# Rover-8_Power_Supply.net
KiCad netlist of a schematic drawn in EAGLE
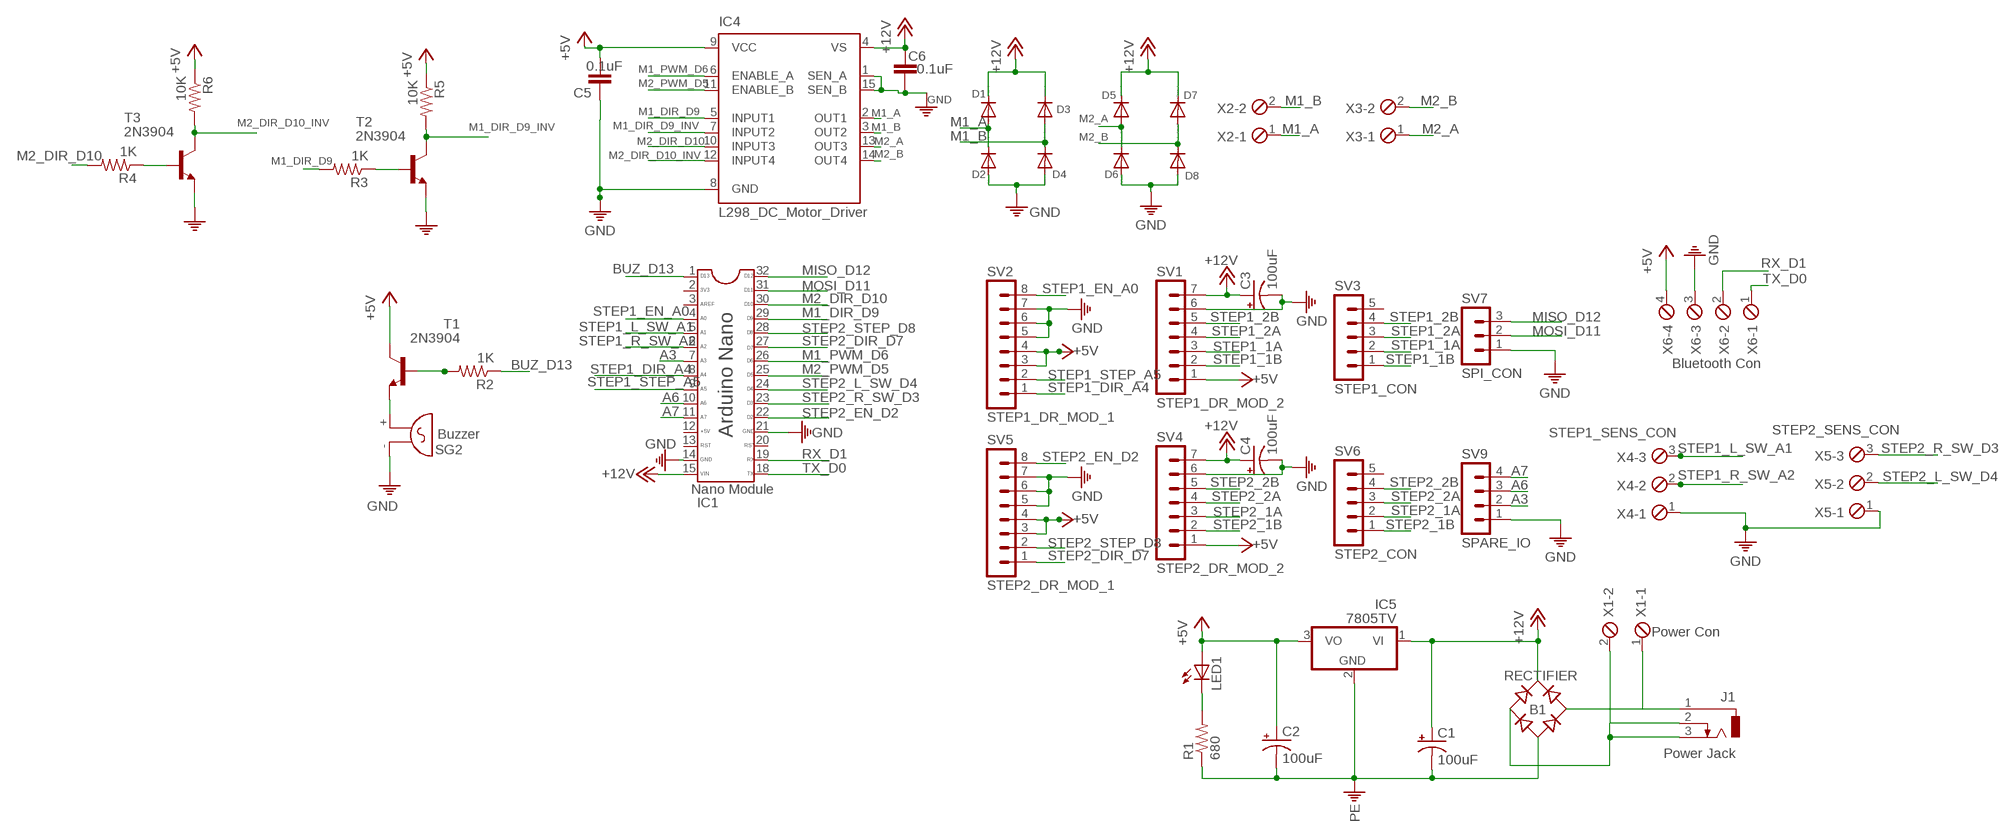
[diagram p0: schematic, sheet 1]

(export (version "E")
  (design (tool "Eeschema 10.0.6"))
  (components
    (comp (ref "B1")
      (value "RECTIFIER")
      (footprint "eagle-import:RB1A")
      (libsource (lib "eagle-import") (part "RB1A"))
    )
    (comp (ref "C1")
      (value "100uF")
      (footprint "eagle-import:E1,8-4")
      (libsource (lib "eagle-import") (part "CPOL-USE1.8-4"))
    )
    (comp (ref "C2")
      (value "100uF")
      (footprint "eagle-import:E1,8-4")
      (libsource (lib "eagle-import") (part "CPOL-USE1.8-4"))
    )
    (comp (ref "C3")
      (value "100uF")
      (footprint "eagle-import:E1,8-4")
      (libsource (lib "eagle-import") (part "CPOL-USE1.8-4"))
    )
    (comp (ref "C4")
      (value "100uF")
      (footprint "eagle-import:E1,8-4")
      (libsource (lib "eagle-import") (part "CPOL-USE1.8-4"))
    )
    (comp (ref "C5")
      (value "0.1uF")
      (footprint "eagle-import:C025-024X044")
      (libsource (lib "eagle-import") (part "C-EU025-024X044"))
    )
    (comp (ref "C6")
      (value "0.1uF")
      (footprint "eagle-import:C025-024X044")
      (libsource (lib "eagle-import") (part "C-EU025-024X044"))
    )
    (comp (ref "D1")
      (value "DIODE-D-2.5")
      (footprint "eagle-import:D-2.5")
      (libsource (lib "eagle-import") (part "DIODE-D-2.5"))
    )
    (comp (ref "D2")
      (value "DIODE-D-2.5")
      (footprint "eagle-import:D-2.5")
      (libsource (lib "eagle-import") (part "DIODE-D-2.5"))
    )
    (comp (ref "D3")
      (value "DIODE-D-2.5")
      (footprint "eagle-import:D-2.5")
      (libsource (lib "eagle-import") (part "DIODE-D-2.5"))
    )
    (comp (ref "D4")
      (value "DIODE-D-2.5")
      (footprint "eagle-import:D-2.5")
      (libsource (lib "eagle-import") (part "DIODE-D-2.5"))
    )
    (comp (ref "D5")
      (value "DIODE-D-2.5")
      (footprint "eagle-import:D-2.5")
      (libsource (lib "eagle-import") (part "DIODE-D-2.5"))
    )
    (comp (ref "D6")
      (value "DIODE-D-2.5")
      (footprint "eagle-import:D-2.5")
      (libsource (lib "eagle-import") (part "DIODE-D-2.5"))
    )
    (comp (ref "D7")
      (value "DIODE-D-2.5")
      (footprint "eagle-import:D-2.5")
      (libsource (lib "eagle-import") (part "DIODE-D-2.5"))
    )
    (comp (ref "D8")
      (value "DIODE-D-2.5")
      (footprint "eagle-import:D-2.5")
      (libsource (lib "eagle-import") (part "DIODE-D-2.5"))
    )
    (comp (ref "IC1")
      (value "Nano Module")
      (footprint "eagle-import:DIL32")
      (libsource (lib "eagle-import") (part "DIL32"))
    )
    (comp (ref "IC4")
      (value "L298_DC_Motor_Driver")
      (footprint "eagle-import:MULTIWATT-15")
      (fields (field (name "MPN") "L298N"))
      (libsource (lib "eagle-import") (part "L298"))
    )
    (comp (ref "IC5")
      (value "7805TV")
      (footprint "eagle-import:TO220V")
      (libsource (lib "eagle-import") (part "78TV05"))
    )
    (comp (ref "J1")
      (value "Power Jack")
      (footprint "eagle-import:ROVER-PW-JACL")
      (libsource (lib "eagle-import") (part "DCJ0303"))
    )
    (comp (ref "LED1")
      (value "LED3MM")
      (footprint "eagle-import:LED3MM")
      (libsource (lib "eagle-import") (part "LED3MM"))
    )
    (comp (ref "R1")
      (value "680")
      (footprint "eagle-import:0204_5")
      (libsource (lib "eagle-import") (part "R-US_0204/5"))
    )
    (comp (ref "R2")
      (value "1K")
      (footprint "eagle-import:0204_5")
      (libsource (lib "eagle-import") (part "R-US_0204/5"))
    )
    (comp (ref "R3")
      (value "1K")
      (footprint "eagle-import:0204_5")
      (libsource (lib "eagle-import") (part "R-US_0204/5"))
    )
    (comp (ref "R4")
      (value "1K")
      (footprint "eagle-import:0204_5")
      (libsource (lib "eagle-import") (part "R-US_0204/5"))
    )
    (comp (ref "R5")
      (value "10K")
      (footprint "eagle-import:0204_5")
      (libsource (lib "eagle-import") (part "R-US_0204/5"))
    )
    (comp (ref "R6")
      (value "10K")
      (footprint "eagle-import:0204_5")
      (libsource (lib "eagle-import") (part "R-US_0204/5"))
    )
    (comp (ref "SG2")
      (value "Buzzer")
      (footprint "eagle-import:F_QMX")
      (libsource (lib "eagle-import") (part "F/QMX"))
    )
    (comp (ref "SV1")
      (value "STEP1_DR_MOD_2")
      (footprint "eagle-import:MA07-1")
      (libsource (lib "eagle-import") (part "MA07-1"))
    )
    (comp (ref "SV2")
      (value "STEP1_DR_MOD_1")
      (footprint "eagle-import:MA08-1")
      (libsource (lib "eagle-import") (part "MA08-1"))
    )
    (comp (ref "SV3")
      (value "STEP1_CON")
      (footprint "eagle-import:MA05-1")
      (libsource (lib "eagle-import") (part "MA05-1"))
    )
    (comp (ref "SV4")
      (value "STEP2_DR_MOD_2")
      (footprint "eagle-import:MA07-1")
      (libsource (lib "eagle-import") (part "MA07-1"))
    )
    (comp (ref "SV5")
      (value "STEP2_DR_MOD_1")
      (footprint "eagle-import:MA08-1")
      (libsource (lib "eagle-import") (part "MA08-1"))
    )
    (comp (ref "SV6")
      (value "STEP2_CON")
      (footprint "eagle-import:MA05-1")
      (libsource (lib "eagle-import") (part "MA05-1"))
    )
    (comp (ref "SV7")
      (value "SPI_CON")
      (footprint "eagle-import:MA03-1")
      (libsource (lib "eagle-import") (part "MA03-1"))
    )
    (comp (ref "SV9")
      (value "SPARE_IO")
      (footprint "eagle-import:MA04-1")
      (libsource (lib "eagle-import") (part "MA04-1"))
    )
    (comp (ref "T1")
      (value "2N3904")
      (footprint "eagle-import:TO92")
      (libsource (lib "eagle-import") (part "2N3904"))
    )
    (comp (ref "T2")
      (value "2N3904")
      (footprint "eagle-import:TO92")
      (libsource (lib "eagle-import") (part "2N3904"))
    )
    (comp (ref "T3")
      (value "2N3904")
      (footprint "eagle-import:TO92")
      (libsource (lib "eagle-import") (part "2N3904"))
    )
    (comp (ref "X1")
      (value "Power Con")
      (footprint "eagle-import:2POL254")
      (libsource (lib "eagle-import") (part "MPT2"))
    )
    (comp (ref "X2")
      (value "MPT2")
      (footprint "eagle-import:2POL254")
      (libsource (lib "eagle-import") (part "MPT2"))
    )
    (comp (ref "X3")
      (value "MPT2")
      (footprint "eagle-import:2POL254")
      (libsource (lib "eagle-import") (part "MPT2"))
    )
    (comp (ref "X4")
      (value "STEP1_SENS_CON")
      (footprint "eagle-import:3POL254")
      (libsource (lib "eagle-import") (part "MPT3"))
    )
    (comp (ref "X5")
      (value "STEP2_SENS_CON")
      (footprint "eagle-import:3POL254")
      (libsource (lib "eagle-import") (part "MPT3"))
    )
    (comp (ref "X6")
      (value "Bluetooth Con")
      (footprint "eagle-import:4POL254")
      (libsource (lib "eagle-import") (part "MPT4"))
    )
  )
  (nets
    (net (code "1") (name "+5V") (class "Default")
      (node (ref "C2") (pin "+") (pinfunction "+_+") (pintype "passive"))
      (node (ref "C5") (pin "2") (pinfunction "2_2") (pintype "passive"))
      (node (ref "IC4") (pin "9") (pinfunction "VCC_9") (pintype "power_in"))
      (node (ref "IC5") (pin "3") (pinfunction "VO_3") (pintype "passive"))
      (node (ref "LED1") (pin "A") (pinfunction "A_A") (pintype "passive"))
      (node (ref "R5") (pin "1") (pinfunction "1_1") (pintype "passive"))
      (node (ref "R6") (pin "1") (pinfunction "1_1") (pintype "passive"))
      (node (ref "SV1") (pin "1") (pinfunction "1_1") (pintype "passive"))
      (node (ref "SV2") (pin "3") (pinfunction "3_3") (pintype "passive"))
      (node (ref "SV2") (pin "4") (pinfunction "4_4") (pintype "passive"))
      (node (ref "SV4") (pin "1") (pinfunction "1_1") (pintype "passive"))
      (node (ref "SV5") (pin "3") (pinfunction "3_3") (pintype "passive"))
      (node (ref "SV5") (pin "4") (pinfunction "4_4") (pintype "passive"))
      (node (ref "T1") (pin "1") (pinfunction "C_1") (pintype "passive"))
      (node (ref "X6") (pin "4") (pinfunction "1_4") (pintype "passive"))
    )
    (net (code "2") (name "+12V") (class "Default")
      (node (ref "B1") (pin "+") (pinfunction "+_+") (pintype "passive"))
      (node (ref "C1") (pin "+") (pinfunction "+_+") (pintype "passive"))
      (node (ref "C3") (pin "+") (pinfunction "+_+") (pintype "passive"))
      (node (ref "C4") (pin "+") (pinfunction "+_+") (pintype "passive"))
      (node (ref "C6") (pin "2") (pinfunction "2_2") (pintype "passive"))
      (node (ref "D1") (pin "C") (pinfunction "C_C") (pintype "passive"))
      (node (ref "D3") (pin "C") (pinfunction "C_C") (pintype "passive"))
      (node (ref "D5") (pin "C") (pinfunction "C_C") (pintype "passive"))
      (node (ref "D7") (pin "C") (pinfunction "C_C") (pintype "passive"))
      (node (ref "IC1") (pin "15") (pinfunction "VIN_15") (pintype "passive"))
      (node (ref "IC4") (pin "4") (pinfunction "VS_4") (pintype "power_in"))
      (node (ref "IC5") (pin "1") (pinfunction "VI_1") (pintype "input"))
      (node (ref "SV1") (pin "7") (pinfunction "7_7") (pintype "passive"))
      (node (ref "SV4") (pin "7") (pinfunction "7_7") (pintype "passive"))
    )
    (net (code "3") (name "/A3") (class "Default")
      (node (ref "IC1") (pin "7") (pinfunction "A3/D17_7") (pintype "passive"))
      (node (ref "SV9") (pin "2") (pinfunction "2_2") (pintype "passive"))
    )
    (net (code "4") (name "/A6") (class "Default")
      (node (ref "IC1") (pin "10") (pinfunction "A6_10") (pintype "passive"))
      (node (ref "SV9") (pin "3") (pinfunction "3_3") (pintype "passive"))
    )
    (net (code "5") (name "/A7") (class "Default")
      (node (ref "IC1") (pin "11") (pinfunction "A7_11") (pintype "passive"))
      (node (ref "SV9") (pin "4") (pinfunction "4_4") (pintype "passive"))
    )
    (net (code "6") (name "/BUZ_D13") (class "Default")
      (node (ref "IC1") (pin "1") (pinfunction "D13_1") (pintype "passive"))
      (node (ref "R2") (pin "1") (pinfunction "1_1") (pintype "passive"))
    )
    (net (code "7") (name "/M1_A") (class "Default")
      (node (ref "D1") (pin "A") (pinfunction "A_A") (pintype "passive"))
      (node (ref "D2") (pin "C") (pinfunction "C_C") (pintype "passive"))
      (node (ref "IC4") (pin "2") (pinfunction "OUT1_2") (pintype "output"))
      (node (ref "X2") (pin "1") (pinfunction "1_1") (pintype "passive"))
    )
    (net (code "8") (name "/M1_B") (class "Default")
      (node (ref "D3") (pin "A") (pinfunction "A_A") (pintype "passive"))
      (node (ref "D4") (pin "C") (pinfunction "C_C") (pintype "passive"))
      (node (ref "IC4") (pin "3") (pinfunction "OUT2_3") (pintype "output"))
      (node (ref "X2") (pin "2") (pinfunction "1_2") (pintype "passive"))
    )
    (net (code "9") (name "/M1_DIR_D9") (class "Default")
      (node (ref "IC1") (pin "29") (pinfunction "D9/PWM_29") (pintype "passive"))
      (node (ref "IC4") (pin "5") (pinfunction "INPUT1_5") (pintype "input"))
      (node (ref "R3") (pin "2") (pinfunction "2_2") (pintype "passive"))
    )
    (net (code "10") (name "/M1_DIR_D9_INV") (class "Default")
      (node (ref "IC4") (pin "7") (pinfunction "INPUT2_7") (pintype "input"))
      (node (ref "R5") (pin "2") (pinfunction "2_2") (pintype "passive"))
      (node (ref "T2") (pin "1") (pinfunction "C_1") (pintype "passive"))
    )
    (net (code "11") (name "/M1_PWM_D6") (class "Default")
      (node (ref "IC1") (pin "26") (pinfunction "D6/PWM_26") (pintype "passive"))
      (node (ref "IC4") (pin "6") (pinfunction "ENABLE_A_6") (pintype "input"))
    )
    (net (code "12") (name "/M2_A") (class "Default")
      (node (ref "D5") (pin "A") (pinfunction "A_A") (pintype "passive"))
      (node (ref "D6") (pin "C") (pinfunction "C_C") (pintype "passive"))
      (node (ref "IC4") (pin "13") (pinfunction "OUT3_13") (pintype "output"))
      (node (ref "X3") (pin "1") (pinfunction "1_1") (pintype "passive"))
    )
    (net (code "13") (name "/M2_B") (class "Default")
      (node (ref "D7") (pin "A") (pinfunction "A_A") (pintype "passive"))
      (node (ref "D8") (pin "C") (pinfunction "C_C") (pintype "passive"))
      (node (ref "IC4") (pin "14") (pinfunction "OUT4_14") (pintype "output"))
      (node (ref "X3") (pin "2") (pinfunction "1_2") (pintype "passive"))
    )
    (net (code "14") (name "/M2_DIR_D10") (class "Default")
      (node (ref "IC1") (pin "30") (pinfunction "D10/PWM_30") (pintype "passive"))
      (node (ref "IC4") (pin "10") (pinfunction "INPUT3_10") (pintype "input"))
      (node (ref "R4") (pin "2") (pinfunction "2_2") (pintype "passive"))
    )
    (net (code "15") (name "/M2_DIR_D10_INV") (class "Default")
      (node (ref "IC4") (pin "12") (pinfunction "INPUT4_12") (pintype "input"))
      (node (ref "R6") (pin "2") (pinfunction "2_2") (pintype "passive"))
      (node (ref "T3") (pin "1") (pinfunction "C_1") (pintype "passive"))
    )
    (net (code "16") (name "/M2_PWM_D5") (class "Default")
      (node (ref "IC1") (pin "25") (pinfunction "D5/PWM_25") (pintype "passive"))
      (node (ref "IC4") (pin "11") (pinfunction "ENABLE_B_11") (pintype "input"))
    )
    (net (code "17") (name "/MISO_D12") (class "Default")
      (node (ref "IC1") (pin "32") (pinfunction "D12/MISO_32") (pintype "passive"))
      (node (ref "SV7") (pin "3") (pinfunction "3_3") (pintype "passive"))
    )
    (net (code "18") (name "/MOSI_D11") (class "Default")
      (node (ref "IC1") (pin "31") (pinfunction "D11/MOSI_31") (pintype "passive"))
      (node (ref "SV7") (pin "2") (pinfunction "2_2") (pintype "passive"))
    )
    (net (code "19") (name "/RX_D1") (class "Default")
      (node (ref "IC1") (pin "19") (pinfunction "RX_19") (pintype "passive"))
      (node (ref "X6") (pin "2") (pinfunction "1_2") (pintype "passive"))
    )
    (net (code "20") (name "/STEP1_1A") (class "Default")
      (node (ref "SV1") (pin "3") (pinfunction "3_3") (pintype "passive"))
      (node (ref "SV3") (pin "2") (pinfunction "2_2") (pintype "passive"))
    )
    (net (code "21") (name "/STEP1_1B") (class "Default")
      (node (ref "SV1") (pin "2") (pinfunction "2_2") (pintype "passive"))
      (node (ref "SV3") (pin "1") (pinfunction "1_1") (pintype "passive"))
    )
    (net (code "22") (name "/STEP1_2A") (class "Default")
      (node (ref "SV1") (pin "4") (pinfunction "4_4") (pintype "passive"))
      (node (ref "SV3") (pin "3") (pinfunction "3_3") (pintype "passive"))
    )
    (net (code "23") (name "/STEP1_2B") (class "Default")
      (node (ref "SV1") (pin "5") (pinfunction "5_5") (pintype "passive"))
      (node (ref "SV3") (pin "4") (pinfunction "4_4") (pintype "passive"))
    )
    (net (code "24") (name "/STEP1_DIR_A4") (class "Default")
      (node (ref "IC1") (pin "8") (pinfunction "A4/D18/SDA_8") (pintype "passive"))
      (node (ref "SV2") (pin "1") (pinfunction "1_1") (pintype "passive"))
    )
    (net (code "25") (name "/STEP1_EN_A0") (class "Default")
      (node (ref "IC1") (pin "4") (pinfunction "A0/D14_4") (pintype "passive"))
      (node (ref "SV2") (pin "8") (pinfunction "8_8") (pintype "passive"))
    )
    (net (code "26") (name "/STEP1_L_SW_A1") (class "Default")
      (node (ref "IC1") (pin "5") (pinfunction "A1/D15_5") (pintype "passive"))
      (node (ref "X4") (pin "3") (pinfunction "1_3") (pintype "passive"))
    )
    (net (code "27") (name "/STEP1_R_SW_A2") (class "Default")
      (node (ref "IC1") (pin "6") (pinfunction "A2/D16_6") (pintype "passive"))
      (node (ref "X4") (pin "2") (pinfunction "1_2") (pintype "passive"))
    )
    (net (code "28") (name "/STEP1_STEP_A5") (class "Default")
      (node (ref "IC1") (pin "9") (pinfunction "A5/D19/SCL_9") (pintype "passive"))
      (node (ref "SV2") (pin "2") (pinfunction "2_2") (pintype "passive"))
    )
    (net (code "29") (name "/STEP2_1A") (class "Default")
      (node (ref "SV4") (pin "3") (pinfunction "3_3") (pintype "passive"))
      (node (ref "SV6") (pin "2") (pinfunction "2_2") (pintype "passive"))
    )
    (net (code "30") (name "/STEP2_1B") (class "Default")
      (node (ref "SV4") (pin "2") (pinfunction "2_2") (pintype "passive"))
      (node (ref "SV6") (pin "1") (pinfunction "1_1") (pintype "passive"))
    )
    (net (code "31") (name "/STEP2_2A") (class "Default")
      (node (ref "SV4") (pin "4") (pinfunction "4_4") (pintype "passive"))
      (node (ref "SV6") (pin "3") (pinfunction "3_3") (pintype "passive"))
    )
    (net (code "32") (name "/STEP2_2B") (class "Default")
      (node (ref "SV4") (pin "5") (pinfunction "5_5") (pintype "passive"))
      (node (ref "SV6") (pin "4") (pinfunction "4_4") (pintype "passive"))
    )
    (net (code "33") (name "/STEP2_DIR_D7") (class "Default")
      (node (ref "IC1") (pin "27") (pinfunction "D7_27") (pintype "passive"))
      (node (ref "SV5") (pin "1") (pinfunction "1_1") (pintype "passive"))
    )
    (net (code "34") (name "/STEP2_EN_D2") (class "Default")
      (node (ref "IC1") (pin "22") (pinfunction "D2_22") (pintype "passive"))
      (node (ref "SV5") (pin "8") (pinfunction "8_8") (pintype "passive"))
    )
    (net (code "35") (name "/STEP2_L_SW_D4") (class "Default")
      (node (ref "IC1") (pin "24") (pinfunction "D4_24") (pintype "passive"))
      (node (ref "X5") (pin "2") (pinfunction "1_2") (pintype "passive"))
    )
    (net (code "36") (name "/STEP2_R_SW_D3") (class "Default")
      (node (ref "IC1") (pin "23") (pinfunction "D3_23") (pintype "passive"))
      (node (ref "X5") (pin "3") (pinfunction "1_3") (pintype "passive"))
    )
    (net (code "37") (name "/STEP2_STEP_D8") (class "Default")
      (node (ref "IC1") (pin "28") (pinfunction "D8_28") (pintype "passive"))
      (node (ref "SV5") (pin "2") (pinfunction "2_2") (pintype "passive"))
    )
    (net (code "38") (name "/TX_D0") (class "Default")
      (node (ref "IC1") (pin "18") (pinfunction "TX_18") (pintype "passive"))
      (node (ref "X6") (pin "1") (pinfunction "1_1") (pintype "passive"))
    )
    (net (code "39") (name "GND") (class "Default")
      (node (ref "B1") (pin "-") (pinfunction "-_-") (pintype "passive"))
      (node (ref "C1") (pin "-") (pinfunction "-_-") (pintype "passive"))
      (node (ref "C2") (pin "-") (pinfunction "-_-") (pintype "passive"))
      (node (ref "C3") (pin "-") (pinfunction "-_-") (pintype "passive"))
      (node (ref "C4") (pin "-") (pinfunction "-_-") (pintype "passive"))
      (node (ref "C5") (pin "1") (pinfunction "1_1") (pintype "passive"))
      (node (ref "C6") (pin "1") (pinfunction "1_1") (pintype "passive"))
      (node (ref "D2") (pin "A") (pinfunction "A_A") (pintype "passive"))
      (node (ref "D4") (pin "A") (pinfunction "A_A") (pintype "passive"))
      (node (ref "D6") (pin "A") (pinfunction "A_A") (pintype "passive"))
      (node (ref "D8") (pin "A") (pinfunction "A_A") (pintype "passive"))
      (node (ref "IC1") (pin "14") (pinfunction "GND1_14") (pintype "passive"))
      (node (ref "IC1") (pin "21") (pinfunction "GND2_21") (pintype "passive"))
      (node (ref "IC4") (pin "1") (pinfunction "SEN_A_1") (pintype "input"))
      (node (ref "IC4") (pin "15") (pinfunction "SEN_B_15") (pintype "input"))
      (node (ref "IC4") (pin "8") (pinfunction "GND_8") (pintype "power_in"))
      (node (ref "IC5") (pin "2") (pinfunction "GND_2") (pintype "passive"))
      (node (ref "R1") (pin "1") (pinfunction "1_1") (pintype "passive"))
      (node (ref "SG2") (pin "-") (pinfunction "1_-") (pintype "passive"))
      (node (ref "SV1") (pin "6") (pinfunction "6_6") (pintype "passive"))
      (node (ref "SV2") (pin "5") (pinfunction "5_5") (pintype "passive"))
      (node (ref "SV2") (pin "6") (pinfunction "6_6") (pintype "passive"))
      (node (ref "SV2") (pin "7") (pinfunction "7_7") (pintype "passive"))
      (node (ref "SV4") (pin "6") (pinfunction "6_6") (pintype "passive"))
      (node (ref "SV5") (pin "5") (pinfunction "5_5") (pintype "passive"))
      (node (ref "SV5") (pin "6") (pinfunction "6_6") (pintype "passive"))
      (node (ref "SV5") (pin "7") (pinfunction "7_7") (pintype "passive"))
      (node (ref "SV7") (pin "1") (pinfunction "1_1") (pintype "passive"))
      (node (ref "SV9") (pin "1") (pinfunction "1_1") (pintype "passive"))
      (node (ref "T2") (pin "3") (pinfunction "E_3") (pintype "passive"))
      (node (ref "T3") (pin "3") (pinfunction "E_3") (pintype "passive"))
      (node (ref "X4") (pin "1") (pinfunction "1_1") (pintype "passive"))
      (node (ref "X5") (pin "1") (pinfunction "1_1") (pintype "passive"))
      (node (ref "X6") (pin "3") (pinfunction "1_3") (pintype "passive"))
    )
    (net (code "40") (name "Net-(B1-PadAC1)") (class "Default")
      (node (ref "B1") (pin "AC1") (pinfunction "AC1_AC1") (pintype "passive"))
      (node (ref "J1") (pin "1") (pinfunction "1_1") (pintype "passive"))
      (node (ref "X1") (pin "1") (pinfunction "1_1") (pintype "passive"))
    )
    (net (code "41") (name "Net-(LED1-C)") (class "Default")
      (node (ref "LED1") (pin "K") (pinfunction "C_K") (pintype "passive"))
      (node (ref "R1") (pin "2") (pinfunction "2_2") (pintype "passive"))
    )
    (net (code "42") (name "Net-(SG2-2)") (class "Default")
      (node (ref "SG2") (pin "+") (pinfunction "2_+") (pintype "passive"))
      (node (ref "T1") (pin "3") (pinfunction "E_3") (pintype "passive"))
    )
    (net (code "43") (name "Net-(T1-B)") (class "Default")
      (node (ref "R2") (pin "2") (pinfunction "2_2") (pintype "passive"))
      (node (ref "T1") (pin "2") (pinfunction "B_2") (pintype "passive"))
    )
    (net (code "44") (name "Net-(T2-B)") (class "Default")
      (node (ref "R3") (pin "1") (pinfunction "1_1") (pintype "passive"))
      (node (ref "T2") (pin "2") (pinfunction "B_2") (pintype "passive"))
    )
    (net (code "45") (name "Net-(T3-B)") (class "Default")
      (node (ref "R4") (pin "1") (pinfunction "1_1") (pintype "passive"))
      (node (ref "T3") (pin "2") (pinfunction "B_2") (pintype "passive"))
    )
    (net (code "46") (name "Net-(X1B-1)") (class "Default")
      (node (ref "B1") (pin "AC2") (pinfunction "AC2_AC2") (pintype "passive"))
      (node (ref "J1") (pin "2") (pinfunction "2_2") (pintype "passive"))
      (node (ref "J1") (pin "3") (pinfunction "3_3") (pintype "passive"))
      (node (ref "X1") (pin "2") (pinfunction "1_2") (pintype "passive"))
    )
    (net (code "47") (name "unconnected-(IC1-3V3-Pad2)") (class "Default")
      (node (ref "IC1") (pin "2") (pinfunction "3V3_2") (pintype "passive"))
    )
    (net (code "48") (name "unconnected-(IC1-5V-Pad12)") (class "Default")
      (node (ref "IC1") (pin "12") (pinfunction "5V_12") (pintype "passive"))
    )
    (net (code "49") (name "unconnected-(IC1-AREF-Pad3)") (class "Default")
      (node (ref "IC1") (pin "3") (pinfunction "AREF_3") (pintype "passive"))
    )
    (net (code "50") (name "unconnected-(IC1-RST1-Pad13)") (class "Default")
      (node (ref "IC1") (pin "13") (pinfunction "RST1_13") (pintype "passive"))
    )
    (net (code "51") (name "unconnected-(IC1-RST2-Pad20)") (class "Default")
      (node (ref "IC1") (pin "20") (pinfunction "RST2_20") (pintype "passive"))
    )
    (net (code "52") (name "unconnected-(SV3-Pad5)") (class "Default")
      (node (ref "SV3") (pin "5") (pinfunction "5_5") (pintype "passive"))
    )
    (net (code "53") (name "unconnected-(SV6-Pad5)") (class "Default")
      (node (ref "SV6") (pin "5") (pinfunction "5_5") (pintype "passive"))
    )
  )
)
